# DRV10987.net
KiCad netlist of a schematic drawn in EAGLE
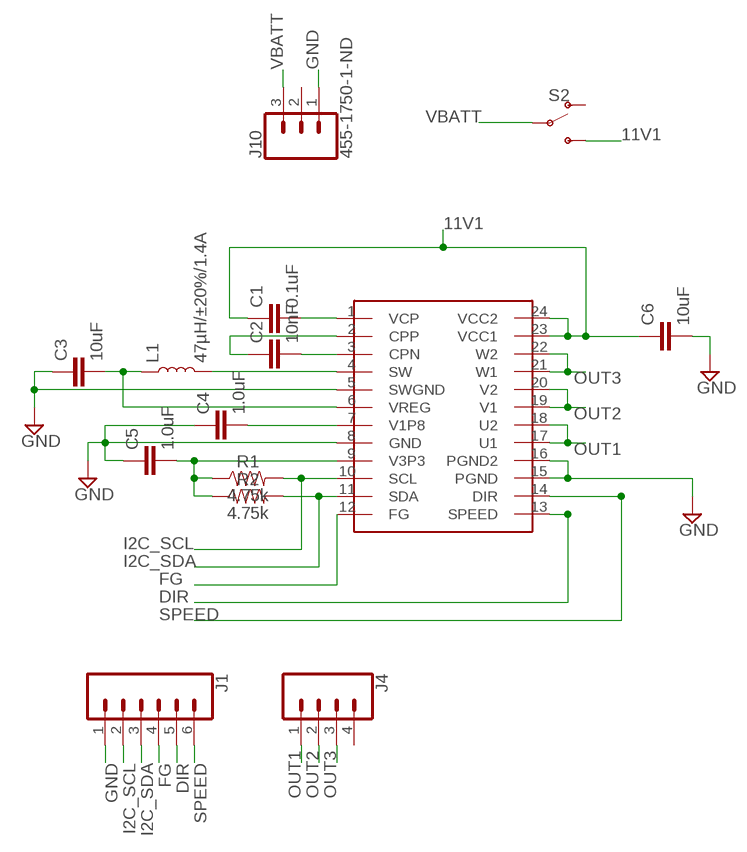
[diagram p0: schematic, sheet 1]

(export (version "E")
  (design (tool "Eeschema 10.0.6"))
  (components
    (comp (ref "C1")
      (value "0.1uF")
      (footprint "eagle-import:0805")
      (libsource (lib "eagle-import") (part "1.0UF-0805-25V-10%"))
    )
    (comp (ref "C2")
      (value "10nF")
      (footprint "eagle-import:0805")
      (libsource (lib "eagle-import") (part "1.0UF-0805-25V-10%"))
    )
    (comp (ref "C3")
      (value "10uF")
      (footprint "eagle-import:0805")
      (libsource (lib "eagle-import") (part "1.0UF-0805-25V-10%"))
    )
    (comp (ref "C4")
      (value "1.0uF")
      (footprint "eagle-import:0805")
      (libsource (lib "eagle-import") (part "1.0UF-0805-25V-10%"))
    )
    (comp (ref "C5")
      (value "1.0uF")
      (footprint "eagle-import:0805")
      (libsource (lib "eagle-import") (part "1.0UF-0805-25V-10%"))
    )
    (comp (ref "C6")
      (value "10uF")
      (footprint "eagle-import:0805")
      (libsource (lib "eagle-import") (part "1.0UF-0805-25V-10%"))
    )
    (comp (ref "J1")
      (value "CONN_06LOCK")
      (footprint "eagle-import:1X06_LOCK")
      (libsource (lib "eagle-import") (part "CONN_06LOCK"))
    )
    (comp (ref "J4")
      (value "CONN_04")
      (footprint "eagle-import:1X04")
      (libsource (lib "eagle-import") (part "CONN_04"))
    )
    (comp (ref "J10")
      (value "455-1750-1-ND")
      (footprint "eagle-import:1X03")
      (libsource (lib "eagle-import") (part "CONN_03"))
    )
    (comp (ref "L1")
      (value "47µH/±20%/1.4A")
      (footprint "eagle-import:SRN6045")
      (libsource (lib "eagle-import") (part "INDUCTOR-SRN6045-33UH"))
    )
    (comp (ref "R1")
      (value "4.75k")
      (footprint "eagle-import:0805")
      (libsource (lib "eagle-import") (part "RESISTOR0805"))
    )
    (comp (ref "R2")
      (value "4.75k")
      (footprint "eagle-import:0805")
      (libsource (lib "eagle-import") (part "RESISTOR0805"))
    )
    (comp (ref "S2")
      (value "SWITCH-SPDT-PTH-11.6X4.0MM")
      (footprint "eagle-import:SWITCH_SPDT_PTH_11.6X4.0MM")
      (libsource (lib "eagle-import") (part "SWITCH-SPDT-PTH-11.6X4.0MM"))
    )
    (comp (ref "U$1")
      (value "DRV10987")
      (footprint "eagle-import:DRV10987")
      (libsource (lib "eagle-import") (part "DRV10987"))
    )
  )
  (nets
    (net (code "1") (name "/11V1") (class "Default")
      (node (ref "C1") (pin "1") (pinfunction "1_1") (pintype "passive"))
      (node (ref "C6") (pin "1") (pinfunction "1_1") (pintype "passive"))
      (node (ref "S2") (pin "3") (pinfunction "S_3") (pintype "passive"))
      (node (ref "U$1") (pin "23") (pinfunction "VCC1_23") (pintype "bidirectional"))
      (node (ref "U$1") (pin "24") (pinfunction "VCC2_24") (pintype "bidirectional"))
    )
    (net (code "2") (name "/DIR") (class "Default")
      (node (ref "J1") (pin "5") (pinfunction "5_5") (pintype "passive"))
      (node (ref "U$1") (pin "13") (pinfunction "SPEED_13") (pintype "bidirectional"))
    )
    (net (code "3") (name "/FG") (class "Default")
      (node (ref "J1") (pin "4") (pinfunction "4_4") (pintype "passive"))
      (node (ref "U$1") (pin "12") (pinfunction "FG_12") (pintype "bidirectional"))
    )
    (net (code "4") (name "/I2C_SCL") (class "Default")
      (node (ref "J1") (pin "2") (pinfunction "2_2") (pintype "passive"))
      (node (ref "R1") (pin "2") (pinfunction "2_2") (pintype "passive"))
      (node (ref "U$1") (pin "10") (pinfunction "SCL_10") (pintype "bidirectional"))
    )
    (net (code "5") (name "/I2C_SDA") (class "Default")
      (node (ref "J1") (pin "3") (pinfunction "3_3") (pintype "passive"))
      (node (ref "R2") (pin "2") (pinfunction "2_2") (pintype "passive"))
      (node (ref "U$1") (pin "11") (pinfunction "SDA_11") (pintype "bidirectional"))
    )
    (net (code "6") (name "/OUT1") (class "Default")
      (node (ref "J4") (pin "1") (pinfunction "1_1") (pintype "passive"))
      (node (ref "U$1") (pin "17") (pinfunction "U1_17") (pintype "bidirectional"))
      (node (ref "U$1") (pin "18") (pinfunction "U2_18") (pintype "bidirectional"))
    )
    (net (code "7") (name "/OUT2") (class "Default")
      (node (ref "J4") (pin "2") (pinfunction "2_2") (pintype "passive"))
      (node (ref "U$1") (pin "19") (pinfunction "V1_19") (pintype "bidirectional"))
      (node (ref "U$1") (pin "20") (pinfunction "V2_20") (pintype "bidirectional"))
    )
    (net (code "8") (name "/OUT3") (class "Default")
      (node (ref "J4") (pin "3") (pinfunction "3_3") (pintype "passive"))
      (node (ref "U$1") (pin "21") (pinfunction "W1_21") (pintype "bidirectional"))
      (node (ref "U$1") (pin "22") (pinfunction "W2_22") (pintype "bidirectional"))
    )
    (net (code "9") (name "/SPEED") (class "Default")
      (node (ref "J1") (pin "6") (pinfunction "6_6") (pintype "passive"))
      (node (ref "U$1") (pin "14") (pinfunction "DIR_14") (pintype "bidirectional"))
    )
    (net (code "10") (name "/VBATT") (class "Default")
      (node (ref "J10") (pin "3") (pinfunction "3_3") (pintype "passive"))
      (node (ref "S2") (pin "2") (pinfunction "P_2") (pintype "passive"))
    )
    (net (code "11") (name "GND") (class "Default")
      (node (ref "C3") (pin "1") (pinfunction "1_1") (pintype "passive"))
      (node (ref "C4") (pin "1") (pinfunction "1_1") (pintype "passive"))
      (node (ref "C5") (pin "1") (pinfunction "1_1") (pintype "passive"))
      (node (ref "C6") (pin "2") (pinfunction "2_2") (pintype "passive"))
      (node (ref "J1") (pin "1") (pinfunction "1_1") (pintype "passive"))
      (node (ref "J10") (pin "1") (pinfunction "1_1") (pintype "passive"))
      (node (ref "U$1") (pin "15") (pinfunction "PGND_15") (pintype "bidirectional"))
      (node (ref "U$1") (pin "16") (pinfunction "PGND2_16") (pintype "bidirectional"))
      (node (ref "U$1") (pin "5") (pinfunction "SWGND_5") (pintype "bidirectional"))
      (node (ref "U$1") (pin "8") (pinfunction "GND_8") (pintype "bidirectional"))
    )
    (net (code "12") (name "Net-(U$1-CPN)") (class "Default")
      (node (ref "C2") (pin "2") (pinfunction "2_2") (pintype "passive"))
      (node (ref "U$1") (pin "3") (pinfunction "CPN_3") (pintype "bidirectional"))
    )
    (net (code "13") (name "Net-(U$1-CPP)") (class "Default")
      (node (ref "C2") (pin "1") (pinfunction "1_1") (pintype "passive"))
      (node (ref "U$1") (pin "2") (pinfunction "CPP_2") (pintype "bidirectional"))
    )
    (net (code "14") (name "Net-(U$1-SW)") (class "Default")
      (node (ref "L1") (pin "2") (pinfunction "2_2") (pintype "passive"))
      (node (ref "U$1") (pin "4") (pinfunction "SW_4") (pintype "bidirectional"))
    )
    (net (code "15") (name "Net-(U$1-V1P8)") (class "Default")
      (node (ref "C4") (pin "2") (pinfunction "2_2") (pintype "passive"))
      (node (ref "U$1") (pin "7") (pinfunction "V1P8_7") (pintype "bidirectional"))
    )
    (net (code "16") (name "Net-(U$1-V3P3)") (class "Default")
      (node (ref "C5") (pin "2") (pinfunction "2_2") (pintype "passive"))
      (node (ref "R1") (pin "1") (pinfunction "1_1") (pintype "passive"))
      (node (ref "R2") (pin "1") (pinfunction "1_1") (pintype "passive"))
      (node (ref "U$1") (pin "9") (pinfunction "V3P3_9") (pintype "bidirectional"))
    )
    (net (code "17") (name "Net-(U$1-VCP)") (class "Default")
      (node (ref "C1") (pin "2") (pinfunction "2_2") (pintype "passive"))
      (node (ref "U$1") (pin "1") (pinfunction "VCP_1") (pintype "bidirectional"))
    )
    (net (code "18") (name "Net-(U$1-VREG)") (class "Default")
      (node (ref "C3") (pin "2") (pinfunction "2_2") (pintype "passive"))
      (node (ref "L1") (pin "1") (pinfunction "1_1") (pintype "passive"))
      (node (ref "U$1") (pin "6") (pinfunction "VREG_6") (pintype "bidirectional"))
    )
    (net (code "19") (name "unconnected-(J4-Pad4)") (class "Default")
      (node (ref "J4") (pin "4") (pinfunction "4_4") (pintype "passive"))
    )
    (net (code "20") (name "unconnected-(J10-Pad2)") (class "Default")
      (node (ref "J10") (pin "2") (pinfunction "2_2") (pintype "passive"))
    )
    (net (code "21") (name "unconnected-(S2-O-Pad1)") (class "Default")
      (node (ref "S2") (pin "1") (pinfunction "O_1") (pintype "passive"))
    )
  )
)
